# source_led.net
KiCad netlist of a schematic drawn in EAGLE
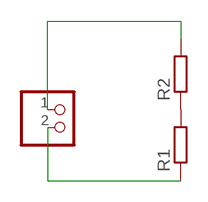
[diagram p0: schematic, sheet 1]

(export (version "E")
  (design (tool "Eeschema 10.0.6"))
  (components
    (comp (ref "JP1")
      (value "PINHD-1X2")
      (footprint "eagle-import:1X02")
      (libsource (lib "eagle-import") (part "PINHD-1X2"))
    )
    (comp (ref "R1")
      (value "R-EU_0204/7")
      (footprint "eagle-import:0204_7")
      (libsource (lib "eagle-import") (part "R-EU_0204/7"))
    )
    (comp (ref "R2")
      (value "R-EU_0204/7")
      (footprint "eagle-import:0204_7")
      (libsource (lib "eagle-import") (part "R-EU_0204/7"))
    )
  )
  (nets
    (net (code "1") (name "Net-(JP1-Pad1)") (class "Default")
      (node (ref "JP1") (pin "1") (pinfunction "1_1") (pintype "passive"))
      (node (ref "R2") (pin "2") (pinfunction "2_2") (pintype "passive"))
    )
    (net (code "2") (name "Net-(JP1-Pad2)") (class "Default")
      (node (ref "JP1") (pin "2") (pinfunction "2_2") (pintype "passive"))
      (node (ref "R1") (pin "1") (pinfunction "1_1") (pintype "passive"))
    )
    (net (code "3") (name "Net-(R1-Pad2)") (class "Default")
      (node (ref "R1") (pin "2") (pinfunction "2_2") (pintype "passive"))
      (node (ref "R2") (pin "1") (pinfunction "1_1") (pintype "passive"))
    )
  )
)
